# picopter_tx.net
KiCad netlist of a schematic drawn in EAGLE
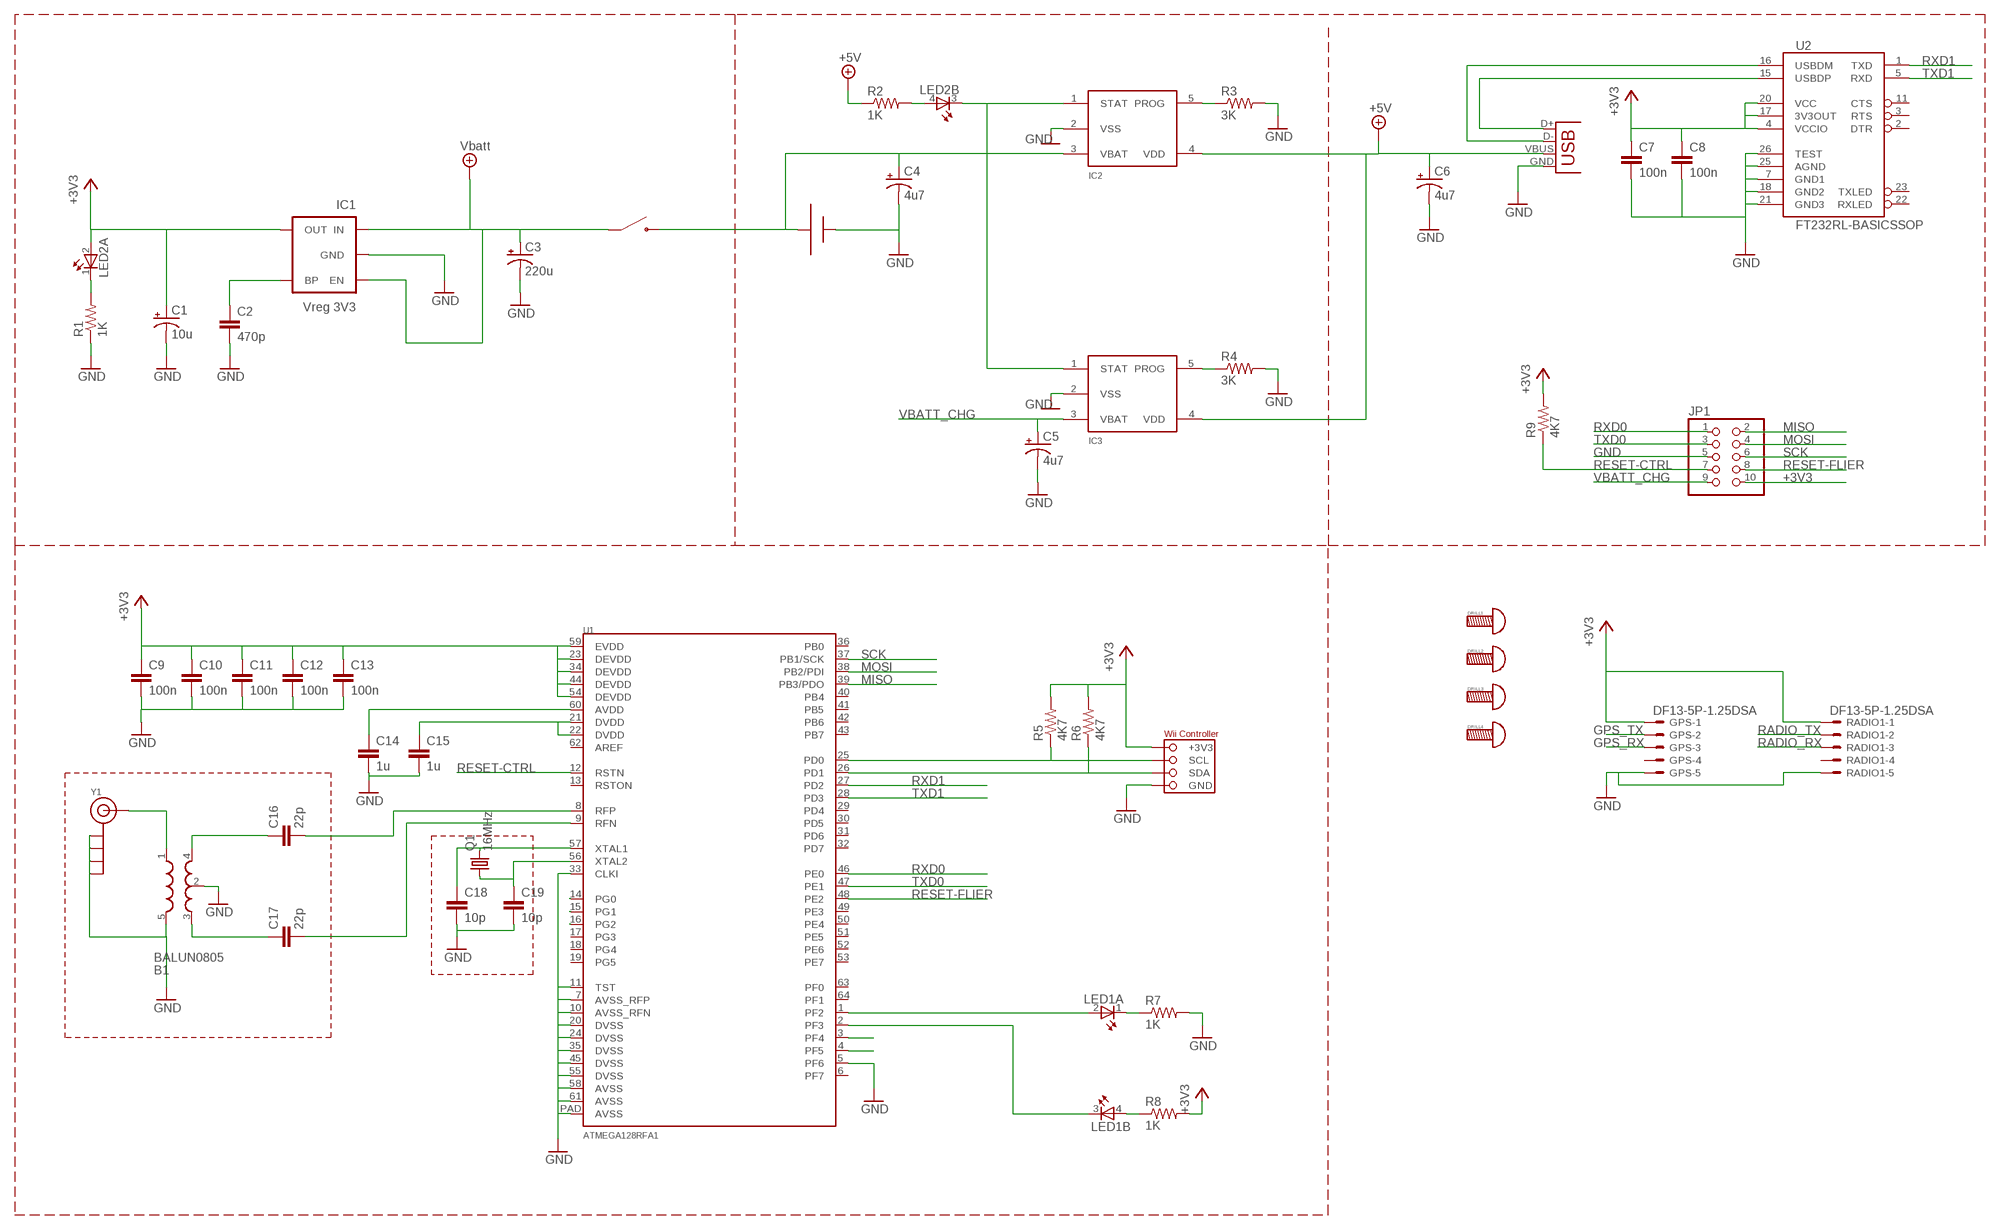
[diagram p0: schematic, sheet 1]

(export (version "E")
  (design (tool "Eeschema 10.0.6"))
  (components
    (comp (ref "B1")
      (value "BALUN0805")
      (footprint "eagle-import:BALUN")
      (libsource (lib "eagle-import") (part "BALUN0805"))
    )
    (comp (ref "BATT2")
      (value "BATT-CONNJST-PH-90")
      (footprint "eagle-import:JST-PH-2-90")
      (libsource (lib "eagle-import") (part "BATT-CONNJST-PH-90"))
    )
    (comp (ref "C1")
      (value "10u")
      (footprint "eagle-import:SMC_B")
      (libsource (lib "eagle-import") (part "CPOL-USSMCB"))
    )
    (comp (ref "C2")
      (value "470p")
      (footprint "eagle-import:C0603")
      (libsource (lib "eagle-import") (part "C-EUC0603"))
    )
    (comp (ref "C3")
      (value "220u")
      (footprint "eagle-import:SMC_B")
      (libsource (lib "eagle-import") (part "CPOL-USSMCB"))
    )
    (comp (ref "C4")
      (value "4u7")
      (footprint "eagle-import:SMC_B")
      (libsource (lib "eagle-import") (part "CPOL-USSMCB"))
    )
    (comp (ref "C5")
      (value "4u7")
      (footprint "eagle-import:SMC_B")
      (libsource (lib "eagle-import") (part "CPOL-USSMCB"))
    )
    (comp (ref "C6")
      (value "4u7")
      (footprint "eagle-import:SMC_B")
      (libsource (lib "eagle-import") (part "CPOL-USSMCB"))
    )
    (comp (ref "C7")
      (value "100n")
      (footprint "eagle-import:C0603")
      (libsource (lib "eagle-import") (part "C-EUC0603"))
    )
    (comp (ref "C8")
      (value "100n")
      (footprint "eagle-import:C0603")
      (libsource (lib "eagle-import") (part "C-EUC0603"))
    )
    (comp (ref "C9")
      (value "100n")
      (footprint "eagle-import:C0603")
      (libsource (lib "eagle-import") (part "C-EUC0603"))
    )
    (comp (ref "C10")
      (value "100n")
      (footprint "eagle-import:C0603")
      (libsource (lib "eagle-import") (part "C-EUC0603"))
    )
    (comp (ref "C11")
      (value "100n")
      (footprint "eagle-import:C0603")
      (libsource (lib "eagle-import") (part "C-EUC0603"))
    )
    (comp (ref "C12")
      (value "100n")
      (footprint "eagle-import:C0603")
      (libsource (lib "eagle-import") (part "C-EUC0603"))
    )
    (comp (ref "C13")
      (value "100n")
      (footprint "eagle-import:C0603")
      (libsource (lib "eagle-import") (part "C-EUC0603"))
    )
    (comp (ref "C14")
      (value "1u")
      (footprint "eagle-import:C0603")
      (libsource (lib "eagle-import") (part "C-EUC0603"))
    )
    (comp (ref "C15")
      (value "1u")
      (footprint "eagle-import:C0603")
      (libsource (lib "eagle-import") (part "C-EUC0603"))
    )
    (comp (ref "C16")
      (value "22p")
      (footprint "eagle-import:C0603")
      (libsource (lib "eagle-import") (part "C-EUC0603"))
    )
    (comp (ref "C17")
      (value "22p")
      (footprint "eagle-import:C0603")
      (libsource (lib "eagle-import") (part "C-EUC0603"))
    )
    (comp (ref "C18")
      (value "10p")
      (footprint "eagle-import:C0603")
      (libsource (lib "eagle-import") (part "C-EUC0603"))
    )
    (comp (ref "C19")
      (value "10p")
      (footprint "eagle-import:C0603")
      (libsource (lib "eagle-import") (part "C-EUC0603"))
    )
    (comp (ref "DRILL1")
      (value "HOLE-4-40")
      (footprint "eagle-import:HOLE-4-40")
      (libsource (lib "eagle-import") (part "HOLE-4-40"))
    )
    (comp (ref "DRILL2")
      (value "HOLE-4-40")
      (footprint "eagle-import:HOLE-4-40")
      (libsource (lib "eagle-import") (part "HOLE-4-40"))
    )
    (comp (ref "DRILL3")
      (value "HOLE-4-40")
      (footprint "eagle-import:HOLE-4-40")
      (libsource (lib "eagle-import") (part "HOLE-4-40"))
    )
    (comp (ref "DRILL4")
      (value "HOLE-4-40")
      (footprint "eagle-import:HOLE-4-40")
      (libsource (lib "eagle-import") (part "HOLE-4-40"))
    )
    (comp (ref "GPS")
      (value "DF13-5P-1.25DSA")
      (footprint "eagle-import:DF13-5P-1.25DSA")
      (libsource (lib "eagle-import") (part "DF13-5P-1.25?DSA"))
    )
    (comp (ref "IC1")
      (value "Vreg 3V3")
      (footprint "eagle-import:SOT23-5")
      (libsource (lib "eagle-import") (part "V_REG_LDOSMD"))
    )
    (comp (ref "IC2")
      (value "MCP-LI-CHARGER-1")
      (footprint "eagle-import:SOT23-5")
      (libsource (lib "eagle-import") (part "MCP-LI-CHARGER-1"))
    )
    (comp (ref "IC3")
      (value "MCP-LI-CHARGER-1")
      (footprint "eagle-import:SOT23-5")
      (libsource (lib "eagle-import") (part "MCP-LI-CHARGER-1"))
    )
    (comp (ref "JP1")
      (value "PINHD-2X5EDGE")
      (footprint "eagle-import:2X5-EDGE")
      (libsource (lib "eagle-import") (part "PINHD-2X5EDGE"))
    )
    (comp (ref "LED1")
      (value "TOPLED-2-CUSTOM")
      (footprint "eagle-import:TOPLED2CUSTOM")
      (libsource (lib "eagle-import") (part "TOPLED-2-CUSTOM"))
    )
    (comp (ref "LED2")
      (value "TOPLED-2-CUSTOM")
      (footprint "eagle-import:TOPLED2CUSTOM")
      (libsource (lib "eagle-import") (part "TOPLED-2-CUSTOM"))
    )
    (comp (ref "Q1")
      (value "16MHz")
      (footprint "eagle-import:CTS406")
      (libsource (lib "eagle-import") (part "CRYSTALCTS406"))
    )
    (comp (ref "R1")
      (value "1K")
      (footprint "eagle-import:R0603")
      (libsource (lib "eagle-import") (part "R-US_R0603"))
    )
    (comp (ref "R2")
      (value "1K")
      (footprint "eagle-import:R0603")
      (libsource (lib "eagle-import") (part "R-US_R0603"))
    )
    (comp (ref "R3")
      (value "3K")
      (footprint "eagle-import:R0603")
      (libsource (lib "eagle-import") (part "R-US_R0603"))
    )
    (comp (ref "R4")
      (value "3K")
      (footprint "eagle-import:R0603")
      (libsource (lib "eagle-import") (part "R-US_R0603"))
    )
    (comp (ref "R5")
      (value "4K7")
      (footprint "eagle-import:R0603")
      (libsource (lib "eagle-import") (part "R-US_R0603"))
    )
    (comp (ref "R6")
      (value "4K7")
      (footprint "eagle-import:R0603")
      (libsource (lib "eagle-import") (part "R-US_R0603"))
    )
    (comp (ref "R7")
      (value "1K")
      (footprint "eagle-import:R0603")
      (libsource (lib "eagle-import") (part "R-US_R0603"))
    )
    (comp (ref "R8")
      (value "1K")
      (footprint "eagle-import:R0603")
      (libsource (lib "eagle-import") (part "R-US_R0603"))
    )
    (comp (ref "R9")
      (value "4K7")
      (footprint "eagle-import:R0603")
      (libsource (lib "eagle-import") (part "R-US_R0603"))
    )
    (comp (ref "RADIO1")
      (value "DF13-5P-1.25DSA")
      (footprint "eagle-import:DF13-5P-1.25DSA")
      (libsource (lib "eagle-import") (part "DF13-5P-1.25?DSA"))
    )
    (comp (ref "S1")
      (value "SWITCH-PWR-CNKOS2")
      (footprint "eagle-import:SWITCH-SPDT-CNK-OS2")
      (libsource (lib "eagle-import") (part "SWITCH-PWR-CNKOS2"))
    )
    (comp (ref "U1")
      (value "ATMEGA128RFA1")
      (footprint "eagle-import:QFN-64")
      (libsource (lib "eagle-import") (part "ATMEGA128RFA1"))
    )
    (comp (ref "U2")
      (value "FT232RL-BASICSSOP")
      (footprint "eagle-import:SSOP28DB")
      (libsource (lib "eagle-import") (part "FT232RL-BASICSSOP"))
    )
    (comp (ref "USB")
      (value "USB-SMD-NS")
      (footprint "eagle-import:USB-MINIB-NOSTOP")
      (libsource (lib "eagle-import") (part "USB-SMD-NS"))
    )
    (comp (ref "X11")
      (value "WII-CONN")
      (footprint "eagle-import:WII-CONN-2")
      (libsource (lib "eagle-import") (part "WII-CONN"))
    )
    (comp (ref "Y1")
      (value "SMA_EDGE")
      (footprint "eagle-import:SMA-EDGE")
      (libsource (lib "eagle-import") (part "SMA_EDGE"))
    )
  )
  (nets
    (net (code "1") (name "+3V3") (class "Default")
      (node (ref "C1") (pin "+") (pinfunction "+_+") (pintype "passive"))
      (node (ref "C10") (pin "1") (pinfunction "1_1") (pintype "passive"))
      (node (ref "C11") (pin "1") (pinfunction "1_1") (pintype "passive"))
      (node (ref "C12") (pin "1") (pinfunction "1_1") (pintype "passive"))
      (node (ref "C13") (pin "1") (pinfunction "1_1") (pintype "passive"))
      (node (ref "C7") (pin "1") (pinfunction "1_1") (pintype "passive"))
      (node (ref "C8") (pin "1") (pinfunction "1_1") (pintype "passive"))
      (node (ref "C9") (pin "1") (pinfunction "1_1") (pintype "passive"))
      (node (ref "GPS") (pin "1") (pinfunction "S_1") (pintype "passive"))
      (node (ref "IC1") (pin "5") (pinfunction "OUT_5") (pintype "passive"))
      (node (ref "JP1") (pin "10") (pinfunction "10_10") (pintype "passive"))
      (node (ref "LED2") (pin "2") (pinfunction "A_2") (pintype "passive"))
      (node (ref "R5") (pin "2") (pinfunction "2_2") (pintype "passive"))
      (node (ref "R6") (pin "2") (pinfunction "2_2") (pintype "passive"))
      (node (ref "R8") (pin "2") (pinfunction "2_2") (pintype "passive"))
      (node (ref "R9") (pin "2") (pinfunction "2_2") (pintype "passive"))
      (node (ref "RADIO1") (pin "1") (pinfunction "S_1") (pintype "passive"))
      (node (ref "U1") (pin "23") (pinfunction "DEVDD_23") (pintype "bidirectional"))
      (node (ref "U1") (pin "34") (pinfunction "DEVDD_34") (pintype "bidirectional"))
      (node (ref "U1") (pin "44") (pinfunction "DEVDD_44") (pintype "bidirectional"))
      (node (ref "U1") (pin "54") (pinfunction "DEVDD_54") (pintype "bidirectional"))
      (node (ref "U1") (pin "59") (pinfunction "EVDD_59") (pintype "bidirectional"))
      (node (ref "U2") (pin "17") (pinfunction "3V3OUT_17") (pintype "output"))
      (node (ref "U2") (pin "20") (pinfunction "VCC_20") (pintype "power_in"))
      (node (ref "U2") (pin "4") (pinfunction "VCCIO_4") (pintype "power_in"))
      (node (ref "X11") (pin "+3V3") (pinfunction "+3V3_+3V3") (pintype "bidirectional"))
    )
    (net (code "2") (name "+5V") (class "Default")
      (node (ref "C6") (pin "+") (pinfunction "+_+") (pintype "passive"))
      (node (ref "IC2") (pin "4") (pinfunction "VDD_4") (pintype "power_in"))
      (node (ref "IC3") (pin "4") (pinfunction "VDD_4") (pintype "power_in"))
      (node (ref "R2") (pin "1") (pinfunction "1_1") (pintype "passive"))
      (node (ref "USB") (pin "VBUS") (pinfunction "VBUS_VBUS") (pintype "bidirectional"))
    )
    (net (code "3") (name "/GPS_RX") (class "Default")
      (node (ref "GPS") (pin "3") (pinfunction "S_3") (pintype "passive"))
    )
    (net (code "4") (name "/GPS_TX") (class "Default")
      (node (ref "GPS") (pin "2") (pinfunction "S_2") (pintype "passive"))
    )
    (net (code "5") (name "/MISO") (class "Default")
      (node (ref "JP1") (pin "2") (pinfunction "2_2") (pintype "passive"))
      (node (ref "U1") (pin "39") (pinfunction "PB3/PDO_39") (pintype "bidirectional"))
    )
    (net (code "6") (name "/MOSI") (class "Default")
      (node (ref "JP1") (pin "4") (pinfunction "4_4") (pintype "passive"))
      (node (ref "U1") (pin "38") (pinfunction "PB2/PDI_38") (pintype "bidirectional"))
    )
    (net (code "7") (name "/RADIO_RX") (class "Default")
      (node (ref "RADIO1") (pin "3") (pinfunction "S_3") (pintype "passive"))
    )
    (net (code "8") (name "/RADIO_TX") (class "Default")
      (node (ref "RADIO1") (pin "2") (pinfunction "S_2") (pintype "passive"))
    )
    (net (code "9") (name "/RESET-CTRL") (class "Default")
      (node (ref "JP1") (pin "7") (pinfunction "7_7") (pintype "passive"))
      (node (ref "R9") (pin "1") (pinfunction "1_1") (pintype "passive"))
      (node (ref "U1") (pin "12") (pinfunction "RSTN_12") (pintype "bidirectional"))
    )
    (net (code "10") (name "/RESET-FLIER") (class "Default")
      (node (ref "JP1") (pin "8") (pinfunction "8_8") (pintype "passive"))
      (node (ref "U1") (pin "48") (pinfunction "PE2_48") (pintype "bidirectional"))
    )
    (net (code "11") (name "/RXD0") (class "Default")
      (node (ref "JP1") (pin "1") (pinfunction "1_1") (pintype "passive"))
      (node (ref "U1") (pin "46") (pinfunction "PE0_46") (pintype "bidirectional"))
    )
    (net (code "12") (name "/RXD1") (class "Default")
      (node (ref "U1") (pin "27") (pinfunction "PD2_27") (pintype "bidirectional"))
      (node (ref "U2") (pin "1") (pinfunction "TXD_1") (pintype "output"))
    )
    (net (code "13") (name "/SCK") (class "Default")
      (node (ref "JP1") (pin "6") (pinfunction "6_6") (pintype "passive"))
      (node (ref "U1") (pin "37") (pinfunction "PB1/SCK_37") (pintype "bidirectional"))
    )
    (net (code "14") (name "/TXD0") (class "Default")
      (node (ref "JP1") (pin "3") (pinfunction "3_3") (pintype "passive"))
      (node (ref "U1") (pin "47") (pinfunction "PE1_47") (pintype "bidirectional"))
    )
    (net (code "15") (name "/TXD1") (class "Default")
      (node (ref "U1") (pin "28") (pinfunction "PD3_28") (pintype "bidirectional"))
      (node (ref "U2") (pin "5") (pinfunction "RXD_5") (pintype "input"))
    )
    (net (code "16") (name "/VBATT_CHG") (class "Default")
      (node (ref "C5") (pin "+") (pinfunction "+_+") (pintype "passive"))
      (node (ref "IC3") (pin "3") (pinfunction "VBAT_3") (pintype "power_in"))
      (node (ref "JP1") (pin "9") (pinfunction "9_9") (pintype "passive"))
    )
    (net (code "17") (name "GND") (class "Default")
      (node (ref "B1") (pin "2") (pinfunction "GND_2") (pintype "bidirectional"))
      (node (ref "B1") (pin "5") (pinfunction "GND_5") (pintype "bidirectional"))
      (node (ref "BATT2") (pin "N") (pinfunction "N_N") (pintype "power_in"))
      (node (ref "C1") (pin "-") (pinfunction "-_-") (pintype "passive"))
      (node (ref "C10") (pin "2") (pinfunction "2_2") (pintype "passive"))
      (node (ref "C11") (pin "2") (pinfunction "2_2") (pintype "passive"))
      (node (ref "C12") (pin "2") (pinfunction "2_2") (pintype "passive"))
      (node (ref "C13") (pin "2") (pinfunction "2_2") (pintype "passive"))
      (node (ref "C14") (pin "2") (pinfunction "2_2") (pintype "passive"))
      (node (ref "C15") (pin "2") (pinfunction "2_2") (pintype "passive"))
      (node (ref "C18") (pin "2") (pinfunction "2_2") (pintype "passive"))
      (node (ref "C19") (pin "2") (pinfunction "2_2") (pintype "passive"))
      (node (ref "C2") (pin "2") (pinfunction "2_2") (pintype "passive"))
      (node (ref "C3") (pin "-") (pinfunction "-_-") (pintype "passive"))
      (node (ref "C4") (pin "-") (pinfunction "-_-") (pintype "passive"))
      (node (ref "C5") (pin "-") (pinfunction "-_-") (pintype "passive"))
      (node (ref "C6") (pin "-") (pinfunction "-_-") (pintype "passive"))
      (node (ref "C7") (pin "2") (pinfunction "2_2") (pintype "passive"))
      (node (ref "C8") (pin "2") (pinfunction "2_2") (pintype "passive"))
      (node (ref "C9") (pin "2") (pinfunction "2_2") (pintype "passive"))
      (node (ref "GPS") (pin "5") (pinfunction "S_5") (pintype "passive"))
      (node (ref "IC1") (pin "2") (pinfunction "GND_2") (pintype "input"))
      (node (ref "IC2") (pin "2") (pinfunction "VSS_2") (pintype "power_in"))
      (node (ref "IC3") (pin "2") (pinfunction "VSS_2") (pintype "power_in"))
      (node (ref "JP1") (pin "5") (pinfunction "5_5") (pintype "passive"))
      (node (ref "R1") (pin "1") (pinfunction "1_1") (pintype "passive"))
      (node (ref "R3") (pin "2") (pinfunction "2_2") (pintype "passive"))
      (node (ref "R4") (pin "2") (pinfunction "2_2") (pintype "passive"))
      (node (ref "R7") (pin "2") (pinfunction "2_2") (pintype "passive"))
      (node (ref "RADIO1") (pin "5") (pinfunction "S_5") (pintype "passive"))
      (node (ref "U1") (pin "10") (pinfunction "AVSS_RFN_10") (pintype "bidirectional"))
      (node (ref "U1") (pin "11") (pinfunction "TST_11") (pintype "bidirectional"))
      (node (ref "U1") (pin "20") (pinfunction "DVSS_20") (pintype "bidirectional"))
      (node (ref "U1") (pin "24") (pinfunction "DVSS_24") (pintype "bidirectional"))
      (node (ref "U1") (pin "33") (pinfunction "CLKI_33") (pintype "bidirectional"))
      (node (ref "U1") (pin "35") (pinfunction "DVSS_35") (pintype "bidirectional"))
      (node (ref "U1") (pin "45") (pinfunction "DVSS_45") (pintype "bidirectional"))
      (node (ref "U1") (pin "5") (pinfunction "PF6_5") (pintype "bidirectional"))
      (node (ref "U1") (pin "55") (pinfunction "DVSS_55") (pintype "bidirectional"))
      (node (ref "U1") (pin "58") (pinfunction "AVSS_58") (pintype "bidirectional"))
      (node (ref "U1") (pin "61") (pinfunction "AVSS_61") (pintype "bidirectional"))
      (node (ref "U1") (pin "7") (pinfunction "AVSS_RFP_7") (pintype "bidirectional"))
      (node (ref "U1") (pin "PAD") (pinfunction "AVSS_PAD") (pintype "bidirectional"))
      (node (ref "U2") (pin "18") (pinfunction "GND2_18") (pintype "power_in"))
      (node (ref "U2") (pin "21") (pinfunction "GND3_21") (pintype "power_in"))
      (node (ref "U2") (pin "25") (pinfunction "AGND_25") (pintype "power_in"))
      (node (ref "U2") (pin "26") (pinfunction "TEST_26") (pintype "input"))
      (node (ref "U2") (pin "7") (pinfunction "GND1_7") (pintype "power_in"))
      (node (ref "USB") (pin "GND") (pinfunction "GND_GND") (pintype "bidirectional"))
      (node (ref "X11") (pin "GND") (pinfunction "GND_GND") (pintype "bidirectional"))
      (node (ref "Y1") (pin "GND@0") (pinfunction "GND_GND@0") (pintype "bidirectional"))
      (node (ref "Y1") (pin "GND@1") (pinfunction "GND_GND@1") (pintype "bidirectional"))
      (node (ref "Y1") (pin "GND@2") (pinfunction "GND_GND@2") (pintype "bidirectional"))
      (node (ref "Y1") (pin "GND@3") (pinfunction "GND_GND@3") (pintype "bidirectional"))
    )
    (net (code "18") (name "Net-(B1-IN)") (class "Default")
      (node (ref "B1") (pin "1") (pinfunction "IN_1") (pintype "bidirectional"))
      (node (ref "Y1") (pin "SIG") (pinfunction "SIGNAL_SIG") (pintype "bidirectional"))
    )
    (net (code "19") (name "Net-(B1-OUT1)") (class "Default")
      (node (ref "B1") (pin "3") (pinfunction "OUT1_3") (pintype "bidirectional"))
      (node (ref "C17") (pin "1") (pinfunction "1_1") (pintype "passive"))
    )
    (net (code "20") (name "Net-(B1-OUT2)") (class "Default")
      (node (ref "B1") (pin "4") (pinfunction "OUT2_4") (pintype "bidirectional"))
      (node (ref "C16") (pin "1") (pinfunction "1_1") (pintype "passive"))
    )
    (net (code "21") (name "Net-(C15-Pad1)") (class "Default")
      (node (ref "C15") (pin "1") (pinfunction "1_1") (pintype "passive"))
      (node (ref "U1") (pin "21") (pinfunction "DVDD_21") (pintype "bidirectional"))
      (node (ref "U1") (pin "22") (pinfunction "DVDD_22") (pintype "bidirectional"))
    )
    (net (code "22") (name "Net-(IC1-BP)") (class "Default")
      (node (ref "C2") (pin "1") (pinfunction "1_1") (pintype "passive"))
      (node (ref "IC1") (pin "4") (pinfunction "BP_4") (pintype "input"))
    )
    (net (code "23") (name "Net-(IC2-PROG)") (class "Default")
      (node (ref "IC2") (pin "5") (pinfunction "PROG_5") (pintype "input"))
      (node (ref "R3") (pin "1") (pinfunction "1_1") (pintype "passive"))
    )
    (net (code "24") (name "Net-(IC2-STAT)") (class "Default")
      (node (ref "IC2") (pin "1") (pinfunction "STAT_1") (pintype "output"))
      (node (ref "IC3") (pin "1") (pinfunction "STAT_1") (pintype "output"))
      (node (ref "LED2") (pin "3") (pinfunction "C_3") (pintype "passive"))
    )
    (net (code "25") (name "Net-(IC2-VBAT)") (class "Default")
      (node (ref "BATT2") (pin "P") (pinfunction "P_P") (pintype "power_in"))
      (node (ref "C4") (pin "+") (pinfunction "+_+") (pintype "passive"))
      (node (ref "IC2") (pin "3") (pinfunction "VBAT_3") (pintype "power_in"))
      (node (ref "S1") (pin "2") (pinfunction "P$2_2") (pintype "passive"))
    )
    (net (code "26") (name "Net-(IC3-PROG)") (class "Default")
      (node (ref "IC3") (pin "5") (pinfunction "PROG_5") (pintype "input"))
      (node (ref "R4") (pin "1") (pinfunction "1_1") (pintype "passive"))
    )
    (net (code "27") (name "Net-(LED1A-A)") (class "Default")
      (node (ref "LED1") (pin "2") (pinfunction "A_2") (pintype "passive"))
      (node (ref "U1") (pin "1") (pinfunction "PF2_1") (pintype "bidirectional"))
    )
    (net (code "28") (name "Net-(LED1A-C)") (class "Default")
      (node (ref "LED1") (pin "1") (pinfunction "C_1") (pintype "passive"))
      (node (ref "R7") (pin "1") (pinfunction "1_1") (pintype "passive"))
    )
    (net (code "29") (name "Net-(LED1B-A)") (class "Default")
      (node (ref "LED1") (pin "4") (pinfunction "A_4") (pintype "passive"))
      (node (ref "R8") (pin "1") (pinfunction "1_1") (pintype "passive"))
    )
    (net (code "30") (name "Net-(LED1B-C)") (class "Default")
      (node (ref "LED1") (pin "3") (pinfunction "C_3") (pintype "passive"))
      (node (ref "U1") (pin "2") (pinfunction "PF3_2") (pintype "bidirectional"))
    )
    (net (code "31") (name "Net-(LED2A-C)") (class "Default")
      (node (ref "LED2") (pin "1") (pinfunction "C_1") (pintype "passive"))
      (node (ref "R1") (pin "2") (pinfunction "2_2") (pintype "passive"))
    )
    (net (code "32") (name "Net-(LED2B-A)") (class "Default")
      (node (ref "LED2") (pin "4") (pinfunction "A_4") (pintype "passive"))
      (node (ref "R2") (pin "2") (pinfunction "2_2") (pintype "passive"))
    )
    (net (code "33") (name "Net-(Q1-2)") (class "Default")
      (node (ref "C18") (pin "1") (pinfunction "1_1") (pintype "passive"))
      (node (ref "Q1") (pin "3") (pinfunction "2_3") (pintype "passive"))
      (node (ref "U1") (pin "57") (pinfunction "XTAL1_57") (pintype "bidirectional"))
    )
    (net (code "34") (name "Net-(U1-AVDD)") (class "Default")
      (node (ref "C14") (pin "1") (pinfunction "1_1") (pintype "passive"))
      (node (ref "U1") (pin "60") (pinfunction "AVDD_60") (pintype "bidirectional"))
    )
    (net (code "35") (name "Net-(U1-PD0)") (class "Default")
      (node (ref "R5") (pin "1") (pinfunction "1_1") (pintype "passive"))
      (node (ref "U1") (pin "25") (pinfunction "PD0_25") (pintype "bidirectional"))
      (node (ref "X11") (pin "SCL") (pinfunction "SCL_SCL") (pintype "bidirectional"))
    )
    (net (code "36") (name "Net-(U1-PD1)") (class "Default")
      (node (ref "R6") (pin "1") (pinfunction "1_1") (pintype "passive"))
      (node (ref "U1") (pin "26") (pinfunction "PD1_26") (pintype "bidirectional"))
      (node (ref "X11") (pin "SDA") (pinfunction "SDA_SDA") (pintype "bidirectional"))
    )
    (net (code "37") (name "Net-(U1-RFN)") (class "Default")
      (node (ref "C17") (pin "2") (pinfunction "2_2") (pintype "passive"))
      (node (ref "U1") (pin "9") (pinfunction "RFN_9") (pintype "bidirectional"))
    )
    (net (code "38") (name "Net-(U1-RFP)") (class "Default")
      (node (ref "C16") (pin "2") (pinfunction "2_2") (pintype "passive"))
      (node (ref "U1") (pin "8") (pinfunction "RFP_8") (pintype "bidirectional"))
    )
    (net (code "39") (name "Net-(U1-XTAL2)") (class "Default")
      (node (ref "C19") (pin "1") (pinfunction "1_1") (pintype "passive"))
      (node (ref "Q1") (pin "1") (pinfunction "1_1") (pintype "passive"))
      (node (ref "U1") (pin "56") (pinfunction "XTAL2_56") (pintype "bidirectional"))
    )
    (net (code "40") (name "Net-(U2-USBDM)") (class "Default")
      (node (ref "U2") (pin "16") (pinfunction "USBDM_16") (pintype "bidirectional"))
      (node (ref "USB") (pin "D-") (pinfunction "D-_D-") (pintype "bidirectional"))
    )
    (net (code "41") (name "Net-(U2-USBDP)") (class "Default")
      (node (ref "U2") (pin "15") (pinfunction "USBDP_15") (pintype "bidirectional"))
      (node (ref "USB") (pin "D+") (pinfunction "D+_D+") (pintype "bidirectional"))
    )
    (net (code "42") (name "Vbatt") (class "Default")
      (node (ref "C3") (pin "+") (pinfunction "+_+") (pintype "passive"))
      (node (ref "IC1") (pin "1") (pinfunction "IN_1") (pintype "input"))
      (node (ref "IC1") (pin "3") (pinfunction "EN_3") (pintype "input"))
      (node (ref "S1") (pin "1") (pinfunction "P$1_1") (pintype "passive"))
    )
    (net (code "43") (name "unconnected-(GPSD-S-Pad4)") (class "Default")
      (node (ref "GPS") (pin "4") (pinfunction "S_4") (pintype "passive"))
    )
    (net (code "44") (name "unconnected-(RADIO1D-S-Pad4)") (class "Default")
      (node (ref "RADIO1") (pin "4") (pinfunction "S_4") (pintype "passive"))
    )
    (net (code "45") (name "unconnected-(U1-AREF-Pad62)") (class "Default")
      (node (ref "U1") (pin "62") (pinfunction "AREF_62") (pintype "bidirectional"))
    )
    (net (code "46") (name "unconnected-(U1-PB0-Pad36)") (class "Default")
      (node (ref "U1") (pin "36") (pinfunction "PB0_36") (pintype "bidirectional"))
    )
    (net (code "47") (name "unconnected-(U1-PB4-Pad40)") (class "Default")
      (node (ref "U1") (pin "40") (pinfunction "PB4_40") (pintype "bidirectional"))
    )
    (net (code "48") (name "unconnected-(U1-PB5-Pad41)") (class "Default")
      (node (ref "U1") (pin "41") (pinfunction "PB5_41") (pintype "bidirectional"))
    )
    (net (code "49") (name "unconnected-(U1-PB6-Pad42)") (class "Default")
      (node (ref "U1") (pin "42") (pinfunction "PB6_42") (pintype "bidirectional"))
    )
    (net (code "50") (name "unconnected-(U1-PB7-Pad43)") (class "Default")
      (node (ref "U1") (pin "43") (pinfunction "PB7_43") (pintype "bidirectional"))
    )
    (net (code "51") (name "unconnected-(U1-PD4-Pad29)") (class "Default")
      (node (ref "U1") (pin "29") (pinfunction "PD4_29") (pintype "bidirectional"))
    )
    (net (code "52") (name "unconnected-(U1-PD5-Pad30)") (class "Default")
      (node (ref "U1") (pin "30") (pinfunction "PD5_30") (pintype "bidirectional"))
    )
    (net (code "53") (name "unconnected-(U1-PD6-Pad31)") (class "Default")
      (node (ref "U1") (pin "31") (pinfunction "PD6_31") (pintype "bidirectional"))
    )
    (net (code "54") (name "unconnected-(U1-PD7-Pad32)") (class "Default")
      (node (ref "U1") (pin "32") (pinfunction "PD7_32") (pintype "bidirectional"))
    )
    (net (code "55") (name "unconnected-(U1-PE3-Pad49)") (class "Default")
      (node (ref "U1") (pin "49") (pinfunction "PE3_49") (pintype "bidirectional"))
    )
    (net (code "56") (name "unconnected-(U1-PE4-Pad50)") (class "Default")
      (node (ref "U1") (pin "50") (pinfunction "PE4_50") (pintype "bidirectional"))
    )
    (net (code "57") (name "unconnected-(U1-PE5-Pad51)") (class "Default")
      (node (ref "U1") (pin "51") (pinfunction "PE5_51") (pintype "bidirectional"))
    )
    (net (code "58") (name "unconnected-(U1-PE6-Pad52)") (class "Default")
      (node (ref "U1") (pin "52") (pinfunction "PE6_52") (pintype "bidirectional"))
    )
    (net (code "59") (name "unconnected-(U1-PE7-Pad53)") (class "Default")
      (node (ref "U1") (pin "53") (pinfunction "PE7_53") (pintype "bidirectional"))
    )
    (net (code "60") (name "unconnected-(U1-PF0-Pad63)") (class "Default")
      (node (ref "U1") (pin "63") (pinfunction "PF0_63") (pintype "bidirectional"))
    )
    (net (code "61") (name "unconnected-(U1-PF1-Pad64)") (class "Default")
      (node (ref "U1") (pin "64") (pinfunction "PF1_64") (pintype "bidirectional"))
    )
    (net (code "62") (name "unconnected-(U1-PF4-Pad3)") (class "Default")
      (node (ref "U1") (pin "3") (pinfunction "PF4_3") (pintype "bidirectional"))
    )
    (net (code "63") (name "unconnected-(U1-PF5-Pad4)") (class "Default")
      (node (ref "U1") (pin "4") (pinfunction "PF5_4") (pintype "bidirectional"))
    )
    (net (code "64") (name "unconnected-(U1-PF7-Pad6)") (class "Default")
      (node (ref "U1") (pin "6") (pinfunction "PF7_6") (pintype "bidirectional"))
    )
    (net (code "65") (name "unconnected-(U1-PG0-Pad14)") (class "Default")
      (node (ref "U1") (pin "14") (pinfunction "PG0_14") (pintype "bidirectional"))
    )
    (net (code "66") (name "unconnected-(U1-PG1-Pad15)") (class "Default")
      (node (ref "U1") (pin "15") (pinfunction "PG1_15") (pintype "bidirectional"))
    )
    (net (code "67") (name "unconnected-(U1-PG2-Pad16)") (class "Default")
      (node (ref "U1") (pin "16") (pinfunction "PG2_16") (pintype "bidirectional"))
    )
    (net (code "68") (name "unconnected-(U1-PG3-Pad17)") (class "Default")
      (node (ref "U1") (pin "17") (pinfunction "PG3_17") (pintype "bidirectional"))
    )
    (net (code "69") (name "unconnected-(U1-PG4-Pad18)") (class "Default")
      (node (ref "U1") (pin "18") (pinfunction "PG4_18") (pintype "bidirectional"))
    )
    (net (code "70") (name "unconnected-(U1-PG5-Pad19)") (class "Default")
      (node (ref "U1") (pin "19") (pinfunction "PG5_19") (pintype "bidirectional"))
    )
    (net (code "71") (name "unconnected-(U1-RSTON-Pad13)") (class "Default")
      (node (ref "U1") (pin "13") (pinfunction "RSTON_13") (pintype "bidirectional"))
    )
    (net (code "72") (name "unconnected-(U2-CTS-Pad11)") (class "Default")
      (node (ref "U2") (pin "11") (pinfunction "CTS_11") (pintype "bidirectional"))
    )
    (net (code "73") (name "unconnected-(U2-DTR-Pad2)") (class "Default")
      (node (ref "U2") (pin "2") (pinfunction "DTR_2") (pintype "bidirectional"))
    )
    (net (code "74") (name "unconnected-(U2-RTS-Pad3)") (class "Default")
      (node (ref "U2") (pin "3") (pinfunction "RTS_3") (pintype "bidirectional"))
    )
    (net (code "75") (name "unconnected-(U2-RXLED-Pad22)") (class "Default")
      (node (ref "U2") (pin "22") (pinfunction "RXLED_22") (pintype "bidirectional"))
    )
    (net (code "76") (name "unconnected-(U2-TXLED-Pad23)") (class "Default")
      (node (ref "U2") (pin "23") (pinfunction "TXLED_23") (pintype "bidirectional"))
    )
  )
)
